# MSGEQ7.net
KiCad netlist of a schematic drawn in EAGLE
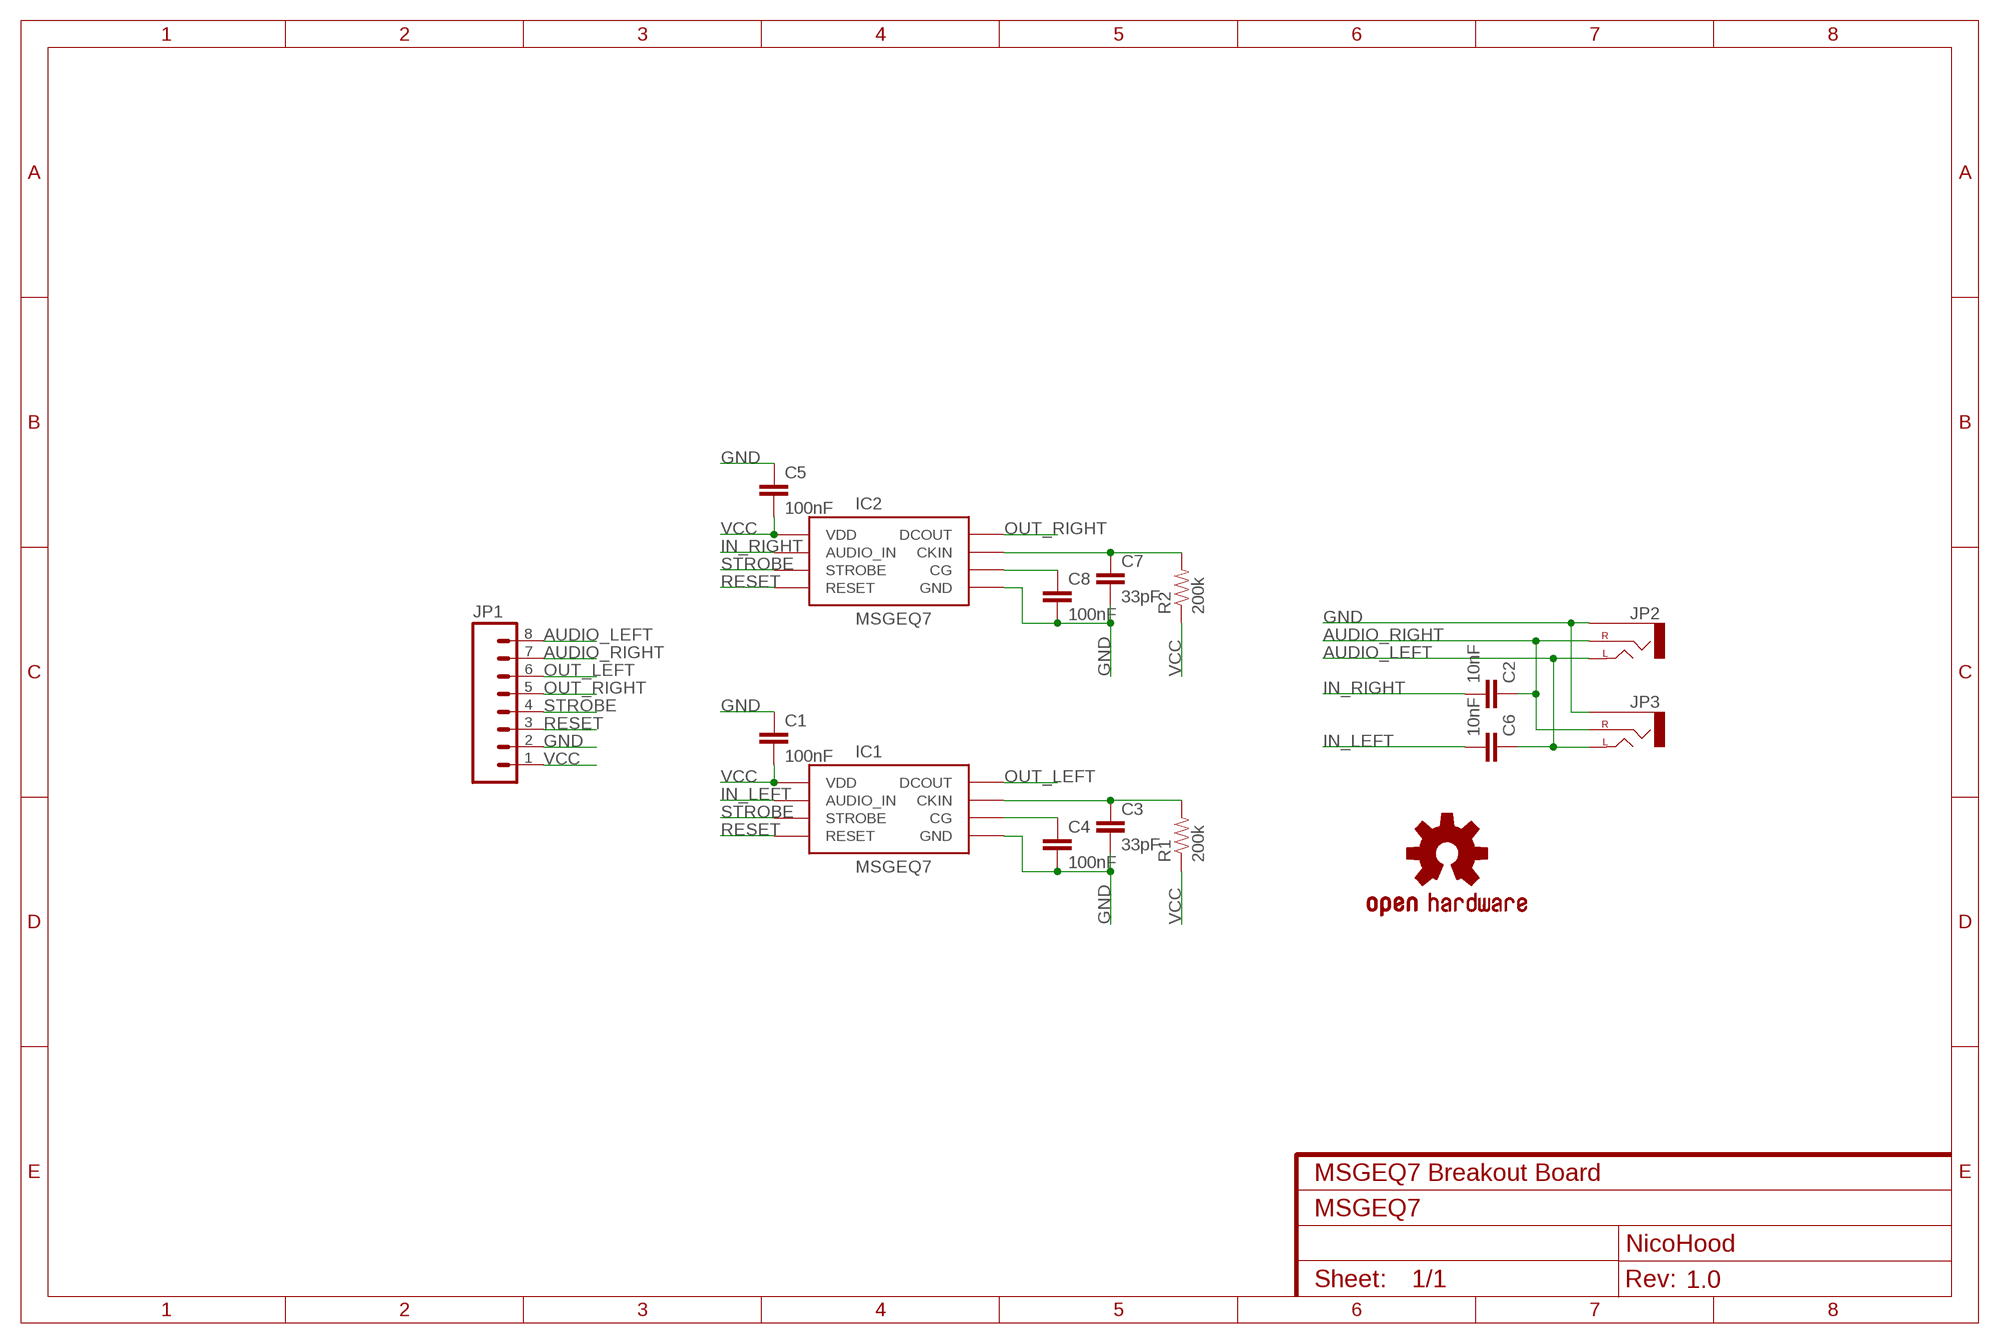
[diagram p0: schematic, sheet 1]

(export (version "E")
  (design (tool "Eeschema 10.0.6"))
  (components
    (comp (ref "C1")
      (value "100nF")
      (footprint "eagle-import:CAP-PTH-SMALL")
      (libsource (lib "eagle-import") (part "CAPPTH"))
    )
    (comp (ref "C2")
      (value "10nF")
      (footprint "eagle-import:CAP-PTH-SMALL")
      (libsource (lib "eagle-import") (part "CAPPTH"))
    )
    (comp (ref "C3")
      (value "33pF")
      (footprint "eagle-import:CAP-PTH-SMALL")
      (libsource (lib "eagle-import") (part "CAPPTH"))
    )
    (comp (ref "C4")
      (value "100nF")
      (footprint "eagle-import:CAP-PTH-SMALL")
      (libsource (lib "eagle-import") (part "CAPPTH"))
    )
    (comp (ref "C5")
      (value "100nF")
      (footprint "eagle-import:CAP-PTH-SMALL")
      (libsource (lib "eagle-import") (part "CAPPTH"))
    )
    (comp (ref "C6")
      (value "10nF")
      (footprint "eagle-import:CAP-PTH-SMALL")
      (libsource (lib "eagle-import") (part "CAPPTH"))
    )
    (comp (ref "C7")
      (value "33pF")
      (footprint "eagle-import:CAP-PTH-SMALL")
      (libsource (lib "eagle-import") (part "CAPPTH"))
    )
    (comp (ref "C8")
      (value "100nF")
      (footprint "eagle-import:CAP-PTH-SMALL")
      (libsource (lib "eagle-import") (part "CAPPTH"))
    )
    (comp (ref "IC1")
      (value "MSGEQ7DIL")
      (footprint "eagle-import:DIL-08")
      (libsource (lib "eagle-import") (part "MSGEQ7DIL"))
    )
    (comp (ref "IC2")
      (value "MSGEQ7DIL")
      (footprint "eagle-import:DIL-08")
      (libsource (lib "eagle-import") (part "MSGEQ7DIL"))
    )
    (comp (ref "JP1")
      (value "M08SILK_FEMALE_PTH")
      (footprint "eagle-import:1X08")
      (libsource (lib "eagle-import") (part "M08SILK_FEMALE_PTH"))
    )
    (comp (ref "JP2")
      (value "AUDIO-JACKPTH")
      (footprint "eagle-import:AUDIO-JACK")
      (libsource (lib "eagle-import") (part "AUDIO-JACKPTH"))
    )
    (comp (ref "JP3")
      (value "AUDIO-JACKPTH")
      (footprint "eagle-import:AUDIO-JACK")
      (libsource (lib "eagle-import") (part "AUDIO-JACKPTH"))
    )
    (comp (ref "LOGO1")
      (value "OSHW-LOGOS")
      (footprint "eagle-import:OSHW-LOGO-S")
      (libsource (lib "eagle-import") (part "OSHW-LOGOS"))
    )
    (comp (ref "R1")
      (value "200k")
      (footprint "eagle-import:AXIAL-0.4")
      (libsource (lib "eagle-import") (part "RESISTORPTH-1/4W"))
    )
    (comp (ref "R2")
      (value "200k")
      (footprint "eagle-import:AXIAL-0.4")
      (libsource (lib "eagle-import") (part "RESISTORPTH-1/4W"))
    )
  )
  (nets
    (net (code "1") (name "/AUDIO_LEFT") (class "Default")
      (node (ref "C6") (pin "1") (pinfunction "1_1") (pintype "passive"))
      (node (ref "JP1") (pin "8") (pinfunction "8_8") (pintype "passive"))
      (node (ref "JP2") (pin "TIP") (pinfunction "LEFT_TIP") (pintype "bidirectional"))
      (node (ref "JP3") (pin "TIP") (pinfunction "LEFT_TIP") (pintype "bidirectional"))
    )
    (net (code "2") (name "/AUDIO_RIGHT") (class "Default")
      (node (ref "C2") (pin "1") (pinfunction "1_1") (pintype "passive"))
      (node (ref "JP1") (pin "7") (pinfunction "7_7") (pintype "passive"))
      (node (ref "JP2") (pin "RING") (pinfunction "RIGHT_RING") (pintype "bidirectional"))
      (node (ref "JP3") (pin "RING") (pinfunction "RIGHT_RING") (pintype "bidirectional"))
    )
    (net (code "3") (name "/GND") (class "Default")
      (node (ref "C1") (pin "1") (pinfunction "1_1") (pintype "passive"))
      (node (ref "C3") (pin "2") (pinfunction "2_2") (pintype "passive"))
      (node (ref "C4") (pin "2") (pinfunction "2_2") (pintype "passive"))
      (node (ref "C5") (pin "1") (pinfunction "1_1") (pintype "passive"))
      (node (ref "C7") (pin "2") (pinfunction "2_2") (pintype "passive"))
      (node (ref "C8") (pin "2") (pinfunction "2_2") (pintype "passive"))
      (node (ref "IC1") (pin "2") (pinfunction "GND_2") (pintype "bidirectional"))
      (node (ref "IC2") (pin "2") (pinfunction "GND_2") (pintype "bidirectional"))
      (node (ref "JP1") (pin "2") (pinfunction "2_2") (pintype "passive"))
      (node (ref "JP2") (pin "SLEEVE") (pinfunction "SLEEVE_SLEEVE") (pintype "bidirectional"))
      (node (ref "JP3") (pin "SLEEVE") (pinfunction "SLEEVE_SLEEVE") (pintype "bidirectional"))
    )
    (net (code "4") (name "/IN_LEFT") (class "Default")
      (node (ref "C6") (pin "2") (pinfunction "2_2") (pintype "passive"))
      (node (ref "IC1") (pin "5") (pinfunction "AUDIO_IN_5") (pintype "input"))
    )
    (net (code "5") (name "/IN_RIGHT") (class "Default")
      (node (ref "C2") (pin "2") (pinfunction "2_2") (pintype "passive"))
      (node (ref "IC2") (pin "5") (pinfunction "AUDIO_IN_5") (pintype "input"))
    )
    (net (code "6") (name "/OUT_LEFT") (class "Default")
      (node (ref "IC1") (pin "3") (pinfunction "DCOUT_3") (pintype "bidirectional"))
      (node (ref "JP1") (pin "6") (pinfunction "6_6") (pintype "passive"))
    )
    (net (code "7") (name "/OUT_RIGHT") (class "Default")
      (node (ref "IC2") (pin "3") (pinfunction "DCOUT_3") (pintype "bidirectional"))
      (node (ref "JP1") (pin "5") (pinfunction "5_5") (pintype "passive"))
    )
    (net (code "8") (name "/RESET") (class "Default")
      (node (ref "IC1") (pin "7") (pinfunction "RESET_7") (pintype "input"))
      (node (ref "IC2") (pin "7") (pinfunction "RESET_7") (pintype "input"))
      (node (ref "JP1") (pin "3") (pinfunction "3_3") (pintype "passive"))
    )
    (net (code "9") (name "/STROBE") (class "Default")
      (node (ref "IC1") (pin "4") (pinfunction "STROBE_4") (pintype "input"))
      (node (ref "IC2") (pin "4") (pinfunction "STROBE_4") (pintype "input"))
      (node (ref "JP1") (pin "4") (pinfunction "4_4") (pintype "passive"))
    )
    (net (code "10") (name "/VCC") (class "Default")
      (node (ref "C1") (pin "2") (pinfunction "2_2") (pintype "passive"))
      (node (ref "C5") (pin "2") (pinfunction "2_2") (pintype "passive"))
      (node (ref "IC1") (pin "1") (pinfunction "VDD_1") (pintype "input"))
      (node (ref "IC2") (pin "1") (pinfunction "VDD_1") (pintype "input"))
      (node (ref "JP1") (pin "1") (pinfunction "1_1") (pintype "passive"))
      (node (ref "R1") (pin "P$1") (pinfunction "1_P$1") (pintype "passive"))
      (node (ref "R2") (pin "P$1") (pinfunction "1_P$1") (pintype "passive"))
    )
    (net (code "11") (name "Net-(IC1-CG)") (class "Default")
      (node (ref "C4") (pin "1") (pinfunction "1_1") (pintype "passive"))
      (node (ref "IC1") (pin "6") (pinfunction "CG_6") (pintype "bidirectional"))
    )
    (net (code "12") (name "Net-(IC1-CKIN)") (class "Default")
      (node (ref "C3") (pin "1") (pinfunction "1_1") (pintype "passive"))
      (node (ref "IC1") (pin "8") (pinfunction "CKIN_8") (pintype "bidirectional"))
      (node (ref "R1") (pin "P$2") (pinfunction "2_P$2") (pintype "passive"))
    )
    (net (code "13") (name "Net-(IC2-CG)") (class "Default")
      (node (ref "C8") (pin "1") (pinfunction "1_1") (pintype "passive"))
      (node (ref "IC2") (pin "6") (pinfunction "CG_6") (pintype "bidirectional"))
    )
    (net (code "14") (name "Net-(IC2-CKIN)") (class "Default")
      (node (ref "C7") (pin "1") (pinfunction "1_1") (pintype "passive"))
      (node (ref "IC2") (pin "8") (pinfunction "CKIN_8") (pintype "bidirectional"))
      (node (ref "R2") (pin "P$2") (pinfunction "2_P$2") (pintype "passive"))
    )
  )
)
